# testbed.net
KiCad netlist of a schematic drawn in EAGLE
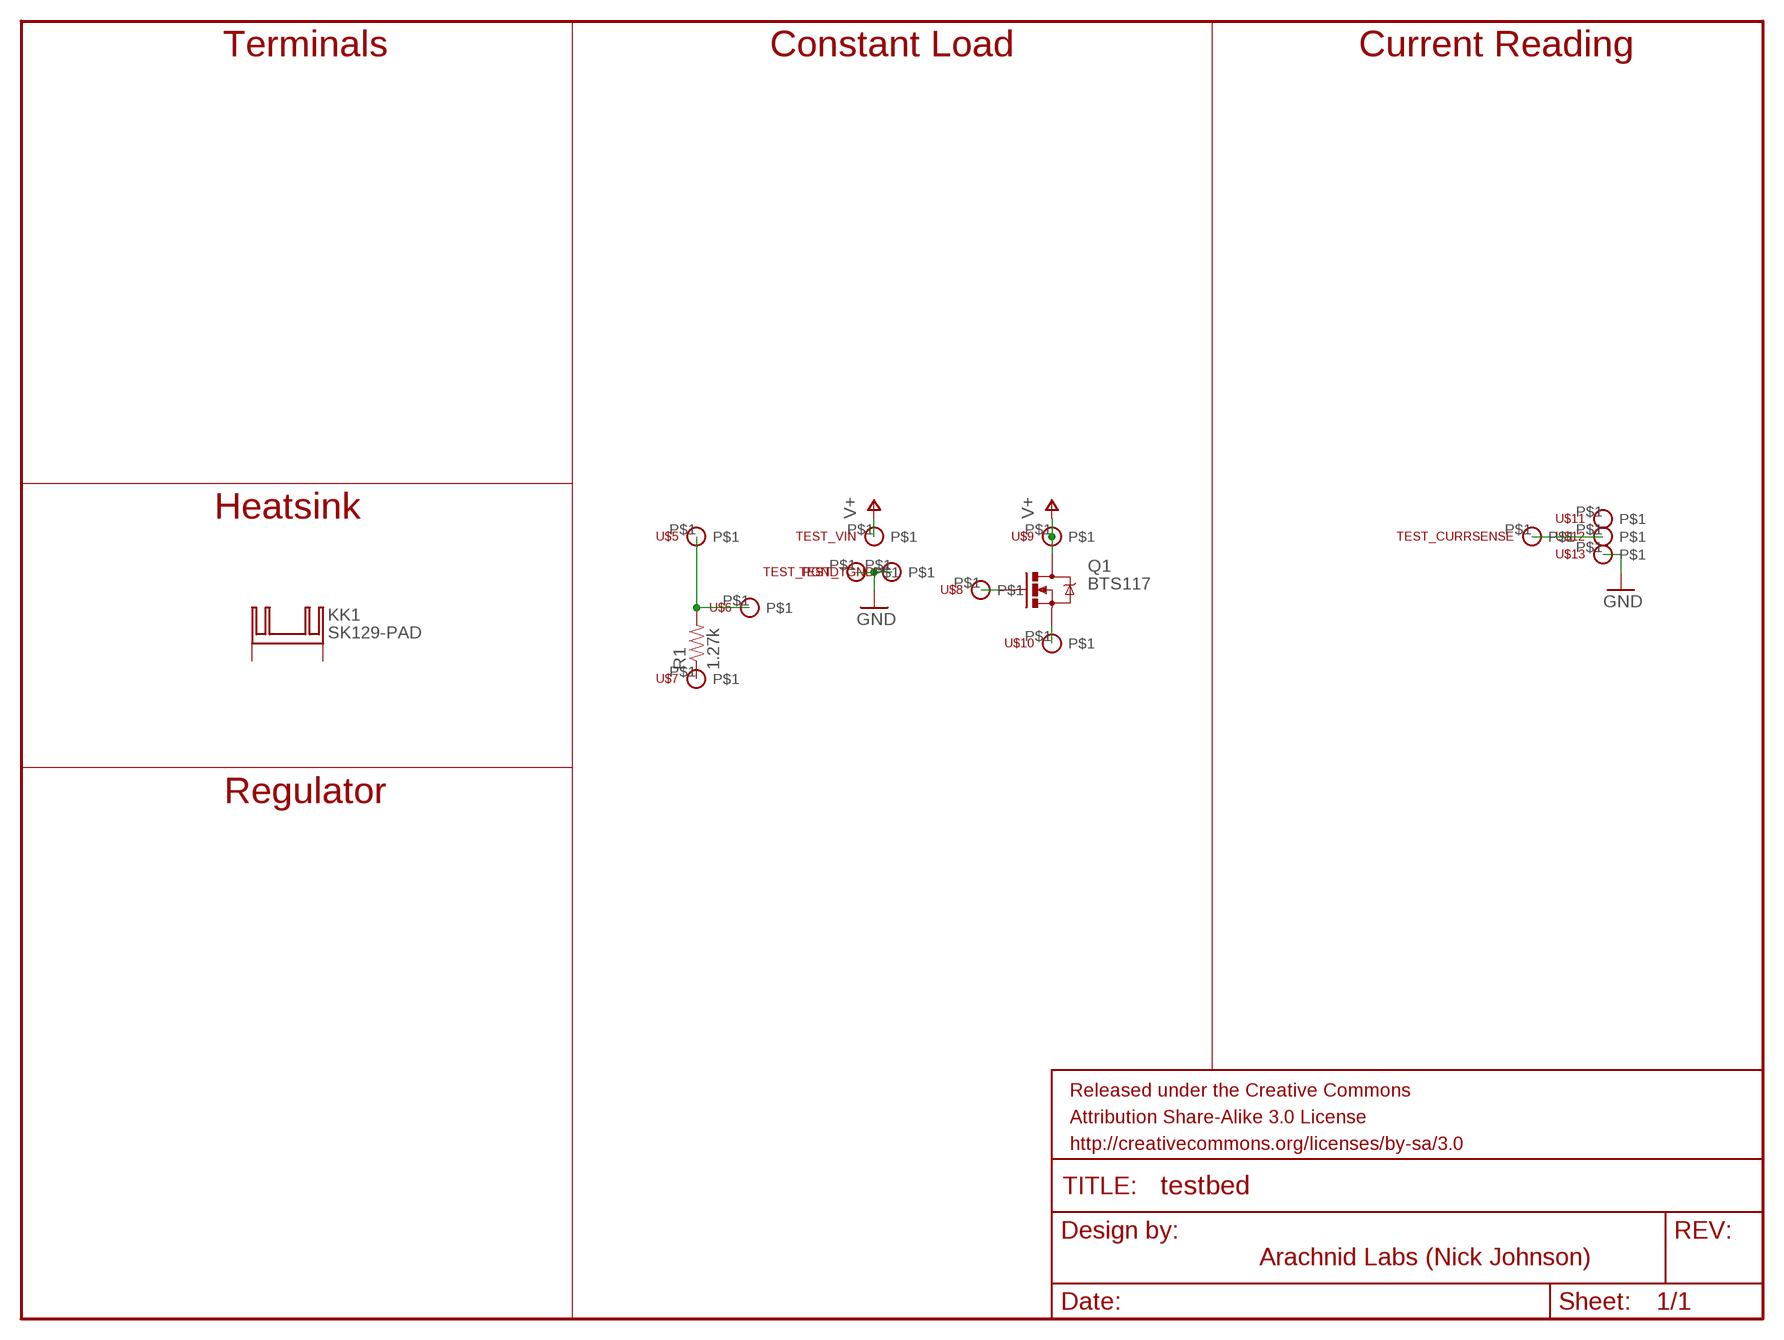
[diagram p0: schematic, sheet 1]

(export (version "E")
  (design (tool "Eeschema 10.0.6"))
  (components
    (comp (ref "KK1")
      (value "SK129-PAD")
      (footprint "eagle-import:SK129")
      (libsource (lib "eagle-import") (part "SK129-PAD"))
    )
    (comp (ref "Q1")
      (value "BTS117")
      (footprint "eagle-import:TO220V")
      (libsource (lib "eagle-import") (part "MOSFET-NCHANNELPTH2"))
    )
    (comp (ref "R1")
      (value "1.27k")
      (footprint "eagle-import:0805")
      (libsource (lib "eagle-import") (part "RESISTOR0805-RES"))
    )
    (comp (ref "TEST_CURRSENSE")
      (value "TEST_POINT")
      (footprint "eagle-import:TEST_POINT")
      (libsource (lib "eagle-import") (part "TEST_POINT"))
    )
    (comp (ref "TEST_PGND")
      (value "TEST_POINT")
      (footprint "eagle-import:TEST_POINT")
      (libsource (lib "eagle-import") (part "TEST_POINT"))
    )
    (comp (ref "TEST_TGND")
      (value "TEST_POINT")
      (footprint "eagle-import:TEST_POINT")
      (libsource (lib "eagle-import") (part "TEST_POINT"))
    )
    (comp (ref "TEST_VIN")
      (value "TEST_POINT")
      (footprint "eagle-import:TEST_POINT")
      (libsource (lib "eagle-import") (part "TEST_POINT"))
    )
    (comp (ref "U$5")
      (value "POGOPIN1.02")
      (footprint "eagle-import:POGOPIN-1.02")
      (libsource (lib "eagle-import") (part "POGOPIN1.02"))
    )
    (comp (ref "U$6")
      (value "POGOPIN1.02")
      (footprint "eagle-import:POGOPIN-1.02")
      (libsource (lib "eagle-import") (part "POGOPIN1.02"))
    )
    (comp (ref "U$7")
      (value "POGOPIN1.02")
      (footprint "eagle-import:POGOPIN-1.02")
      (libsource (lib "eagle-import") (part "POGOPIN1.02"))
    )
    (comp (ref "U$8")
      (value "POGOPIN1.02")
      (footprint "eagle-import:POGOPIN-1.02")
      (libsource (lib "eagle-import") (part "POGOPIN1.02"))
    )
    (comp (ref "U$9")
      (value "POGOPIN1.02")
      (footprint "eagle-import:POGOPIN-1.02")
      (libsource (lib "eagle-import") (part "POGOPIN1.02"))
    )
    (comp (ref "U$10")
      (value "POGOPIN1.02")
      (footprint "eagle-import:POGOPIN-1.02")
      (libsource (lib "eagle-import") (part "POGOPIN1.02"))
    )
    (comp (ref "U$11")
      (value "POGOPIN1.02")
      (footprint "eagle-import:POGOPIN-1.02")
      (libsource (lib "eagle-import") (part "POGOPIN1.02"))
    )
    (comp (ref "U$12")
      (value "POGOPIN1.02")
      (footprint "eagle-import:POGOPIN-1.02")
      (libsource (lib "eagle-import") (part "POGOPIN1.02"))
    )
    (comp (ref "U$13")
      (value "POGOPIN1.02")
      (footprint "eagle-import:POGOPIN-1.02")
      (libsource (lib "eagle-import") (part "POGOPIN1.02"))
    )
  )
  (nets
    (net (code "1") (name "GND") (class "Default")
      (node (ref "TEST_PGND") (pin "P$1") (pinfunction "P$1_P$1") (pintype "passive"))
      (node (ref "TEST_TGND") (pin "P$1") (pinfunction "P$1_P$1") (pintype "passive"))
      (node (ref "U$13") (pin "P$1") (pinfunction "P$1_P$1") (pintype "passive"))
    )
    (net (code "2") (name "Net-(Q1-G)") (class "Default")
      (node (ref "Q1") (pin "1") (pinfunction "G_1") (pintype "passive"))
      (node (ref "U$8") (pin "P$1") (pinfunction "P$1_P$1") (pintype "passive"))
    )
    (net (code "3") (name "Net-(Q1-S)") (class "Default")
      (node (ref "Q1") (pin "3") (pinfunction "S_3") (pintype "passive"))
      (node (ref "U$10") (pin "P$1") (pinfunction "P$1_P$1") (pintype "passive"))
    )
    (net (code "4") (name "Net-(R1-Pad1)") (class "Default")
      (node (ref "R1") (pin "1") (pinfunction "1_1") (pintype "passive"))
      (node (ref "U$7") (pin "P$1") (pinfunction "P$1_P$1") (pintype "passive"))
    )
    (net (code "5") (name "Net-(R1-Pad2)") (class "Default")
      (node (ref "R1") (pin "2") (pinfunction "2_2") (pintype "passive"))
      (node (ref "U$5") (pin "P$1") (pinfunction "P$1_P$1") (pintype "passive"))
      (node (ref "U$6") (pin "P$1") (pinfunction "P$1_P$1") (pintype "passive"))
    )
    (net (code "6") (name "Net-(TEST_CURRSENSE-PadP$1)") (class "Default")
      (node (ref "TEST_CURRSENSE") (pin "P$1") (pinfunction "P$1_P$1") (pintype "passive"))
      (node (ref "U$12") (pin "P$1") (pinfunction "P$1_P$1") (pintype "passive"))
    )
    (net (code "7") (name "V+") (class "Default")
      (node (ref "Q1") (pin "2") (pinfunction "D_2") (pintype "passive"))
      (node (ref "TEST_VIN") (pin "P$1") (pinfunction "P$1_P$1") (pintype "passive"))
      (node (ref "U$9") (pin "P$1") (pinfunction "P$1_P$1") (pintype "passive"))
    )
    (net (code "8") (name "unconnected-(KK1-K-PadA2,5)") (class "Default")
      (node (ref "KK1") (pin "A2,5") (pinfunction "K_A2,5") (pintype "passive"))
    )
    (net (code "9") (name "unconnected-(KK1-K-PadB2,5)") (class "Default")
      (node (ref "KK1") (pin "B2,5") (pinfunction "K_B2,5") (pintype "passive"))
    )
    (net (code "10") (name "unconnected-(U$11-PadP$1)") (class "Default")
      (node (ref "U$11") (pin "P$1") (pinfunction "P$1_P$1") (pintype "passive"))
    )
  )
)
